# LV.net
KiCad netlist of a schematic drawn in Altium Designer
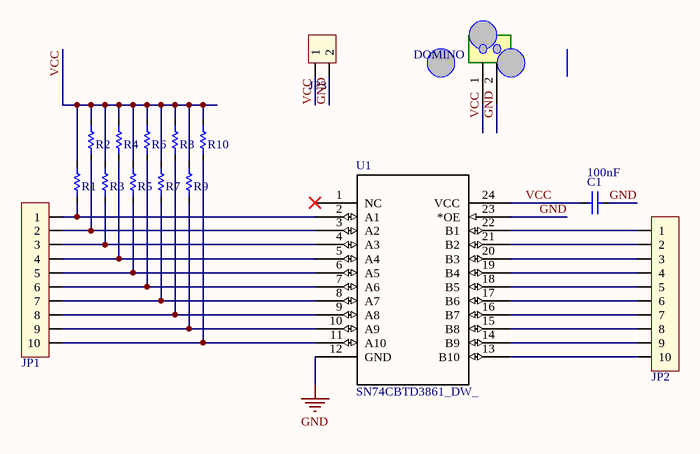
[diagram p0: LV.SchDoc]

(export (version "E")
  (design (tool "Eeschema 10.0.6"))
  (components
    (comp (ref "C1")
      (value "100nF")
      (footprint "0805_C")
      (description "0805 SMD capacitor")
      (libsource (lib "HungIntegrated_Library") (part "C"))
    )
    (comp (ref "D1") (value "DOMINO") (footprint "DOMINO2") (libsource (lib "Thach") (part "Domino 2")))
    (comp (ref "JP1")
      (value "JP10")
      (footprint "HEAD10")
      (description "Connector 10")
      (libsource (lib "") (part "HEAD10_1"))
    )
    (comp (ref "JP2")
      (value "JP10")
      (footprint "HEAD10")
      (description "Connector 10")
      (libsource (lib "Thach") (part "HEAD10"))
    )
    (comp (ref "JP3")
      (value "JP2")
      (footprint "HEAD2")
      (description "Connector 2")
      (libsource (lib "Thach") (part "HEAD2"))
    )
    (comp (ref "R1")
      (value "0805_R")
      (footprint "0805_R")
      (description "0805 SMD resistor")
      (libsource (lib "Thach") (part "0805_R"))
    )
    (comp (ref "R2")
      (value "0805_R")
      (footprint "0805_R")
      (description "0805 SMD resistor")
      (libsource (lib "Thach") (part "0805_R"))
    )
    (comp (ref "R3")
      (value "0805_R")
      (footprint "0805_R")
      (description "0805 SMD resistor")
      (libsource (lib "Thach") (part "0805_R"))
    )
    (comp (ref "R4")
      (value "0805_R")
      (footprint "0805_R")
      (description "0805 SMD resistor")
      (libsource (lib "Thach") (part "0805_R"))
    )
    (comp (ref "R5")
      (value "0805_R")
      (footprint "0805_R")
      (description "0805 SMD resistor")
      (libsource (lib "Thach") (part "0805_R"))
    )
    (comp (ref "R6")
      (value "0805_R")
      (footprint "0805_R")
      (description "0805 SMD resistor")
      (libsource (lib "Thach") (part "0805_R"))
    )
    (comp (ref "R7")
      (value "0805_R")
      (footprint "0805_R")
      (description "0805 SMD resistor")
      (libsource (lib "Thach") (part "0805_R"))
    )
    (comp (ref "R8")
      (value "0805_R")
      (footprint "0805_R")
      (description "0805 SMD resistor")
      (libsource (lib "Thach") (part "0805_R"))
    )
    (comp (ref "R9")
      (value "0805_R")
      (footprint "0805_R")
      (description "0805 SMD resistor")
      (libsource (lib "Thach") (part "0805_R"))
    )
    (comp (ref "R10")
      (value "0805_R")
      (footprint "0805_R")
      (description "0805 SMD resistor")
      (libsource (lib "Thach") (part "0805_R"))
    )
    (comp (ref "U1")
      (value "SN74CBTD3861_DW_")
      (footprint "DW24-M")
      (description "Imported")
      (fields
        (field (name "MANUFACTURER") "Texas Instruments")
        (field (name "GENERIC_PART_NUMBER") "SN74CBTD3861")
      )
      (libsource (lib "Thach") (part "SN74CBTD3861_DW_"))
    )
  )
  (nets
    (net (code "1") (name "/VCC") (class "Default")
      (node (ref "C1") (pin "1") (pinfunction "1_1") (pintype "passive"))
      (node (ref "D1") (pin "1") (pintype "passive"))
      (node (ref "JP3") (pin "1") (pinfunction "1_1") (pintype "passive"))
      (node (ref "R1") (pin "1") (pinfunction "1_1") (pintype "passive"))
      (node (ref "R10") (pin "1") (pinfunction "1_1") (pintype "passive"))
      (node (ref "R2") (pin "1") (pinfunction "1_1") (pintype "passive"))
      (node (ref "R3") (pin "1") (pinfunction "1_1") (pintype "passive"))
      (node (ref "R4") (pin "1") (pinfunction "1_1") (pintype "passive"))
      (node (ref "R5") (pin "1") (pinfunction "1_1") (pintype "passive"))
      (node (ref "R6") (pin "1") (pinfunction "1_1") (pintype "passive"))
      (node (ref "R7") (pin "1") (pinfunction "1_1") (pintype "passive"))
      (node (ref "R8") (pin "1") (pinfunction "1_1") (pintype "passive"))
      (node (ref "R9") (pin "1") (pinfunction "1_1") (pintype "passive"))
      (node (ref "U1") (pin "24") (pinfunction "VCC_24") (pintype "power_in"))
    )
    (net (code "2") (name "GND") (class "Default")
      (node (ref "C1") (pin "2") (pinfunction "2_2") (pintype "passive"))
      (node (ref "D1") (pin "2") (pintype "passive"))
      (node (ref "JP3") (pin "2") (pinfunction "2_2") (pintype "passive"))
      (node (ref "U1") (pin "12") (pinfunction "GND_12") (pintype "power_in"))
      (node (ref "U1") (pin "23") (pinfunction "*OE_23") (pintype "input"))
    )
    (net (code "3") (name "Net-(U1-A1)") (class "Default")
      (node (ref "JP1") (pin "1") (pinfunction "1_1") (pintype "passive"))
      (node (ref "R1") (pin "2") (pinfunction "2_2") (pintype "passive"))
      (node (ref "U1") (pin "2") (pinfunction "A1_2") (pintype "bidirectional"))
    )
    (net (code "4") (name "Net-(U1-A2)") (class "Default")
      (node (ref "JP1") (pin "2") (pinfunction "2_2") (pintype "passive"))
      (node (ref "R2") (pin "2") (pinfunction "2_2") (pintype "passive"))
      (node (ref "U1") (pin "3") (pinfunction "A2_3") (pintype "bidirectional"))
    )
    (net (code "5") (name "Net-(U1-A3)") (class "Default")
      (node (ref "JP1") (pin "3") (pinfunction "3_3") (pintype "passive"))
      (node (ref "R3") (pin "2") (pinfunction "2_2") (pintype "passive"))
      (node (ref "U1") (pin "4") (pinfunction "A3_4") (pintype "bidirectional"))
    )
    (net (code "6") (name "Net-(U1-A4)") (class "Default")
      (node (ref "JP1") (pin "4") (pinfunction "4_4") (pintype "passive"))
      (node (ref "R4") (pin "2") (pinfunction "2_2") (pintype "passive"))
      (node (ref "U1") (pin "5") (pinfunction "A4_5") (pintype "bidirectional"))
    )
    (net (code "7") (name "Net-(U1-A5)") (class "Default")
      (node (ref "JP1") (pin "5") (pinfunction "5_5") (pintype "passive"))
      (node (ref "R5") (pin "2") (pinfunction "2_2") (pintype "passive"))
      (node (ref "U1") (pin "6") (pinfunction "A5_6") (pintype "bidirectional"))
    )
    (net (code "8") (name "Net-(U1-A6)") (class "Default")
      (node (ref "JP1") (pin "6") (pinfunction "6_6") (pintype "passive"))
      (node (ref "R6") (pin "2") (pinfunction "2_2") (pintype "passive"))
      (node (ref "U1") (pin "7") (pinfunction "A6_7") (pintype "bidirectional"))
    )
    (net (code "9") (name "Net-(U1-A7)") (class "Default")
      (node (ref "JP1") (pin "7") (pinfunction "7_7") (pintype "passive"))
      (node (ref "R7") (pin "2") (pinfunction "2_2") (pintype "passive"))
      (node (ref "U1") (pin "8") (pinfunction "A7_8") (pintype "bidirectional"))
    )
    (net (code "10") (name "Net-(U1-A8)") (class "Default")
      (node (ref "JP1") (pin "8") (pinfunction "8_8") (pintype "passive"))
      (node (ref "R8") (pin "2") (pinfunction "2_2") (pintype "passive"))
      (node (ref "U1") (pin "9") (pinfunction "A8_9") (pintype "bidirectional"))
    )
    (net (code "11") (name "Net-(U1-A9)") (class "Default")
      (node (ref "JP1") (pin "9") (pinfunction "9_9") (pintype "passive"))
      (node (ref "R9") (pin "2") (pinfunction "2_2") (pintype "passive"))
      (node (ref "U1") (pin "10") (pinfunction "A9_10") (pintype "bidirectional"))
    )
    (net (code "12") (name "Net-(U1-A10)") (class "Default")
      (node (ref "JP1") (pin "10") (pinfunction "10_10") (pintype "passive"))
      (node (ref "R10") (pin "2") (pinfunction "2_2") (pintype "passive"))
      (node (ref "U1") (pin "11") (pinfunction "A10_11") (pintype "bidirectional"))
    )
    (net (code "13") (name "Net-(U1-B1)") (class "Default")
      (node (ref "JP2") (pin "1") (pinfunction "1_1") (pintype "passive"))
      (node (ref "U1") (pin "22") (pinfunction "B1_22") (pintype "bidirectional"))
    )
    (net (code "14") (name "Net-(U1-B2)") (class "Default")
      (node (ref "JP2") (pin "2") (pinfunction "2_2") (pintype "passive"))
      (node (ref "U1") (pin "21") (pinfunction "B2_21") (pintype "bidirectional"))
    )
    (net (code "15") (name "Net-(U1-B3)") (class "Default")
      (node (ref "JP2") (pin "3") (pinfunction "3_3") (pintype "passive"))
      (node (ref "U1") (pin "20") (pinfunction "B3_20") (pintype "bidirectional"))
    )
    (net (code "16") (name "Net-(U1-B4)") (class "Default")
      (node (ref "JP2") (pin "4") (pinfunction "4_4") (pintype "passive"))
      (node (ref "U1") (pin "19") (pinfunction "B4_19") (pintype "bidirectional"))
    )
    (net (code "17") (name "Net-(U1-B5)") (class "Default")
      (node (ref "JP2") (pin "5") (pinfunction "5_5") (pintype "passive"))
      (node (ref "U1") (pin "18") (pinfunction "B5_18") (pintype "bidirectional"))
    )
    (net (code "18") (name "Net-(U1-B6)") (class "Default")
      (node (ref "JP2") (pin "6") (pinfunction "6_6") (pintype "passive"))
      (node (ref "U1") (pin "17") (pinfunction "B6_17") (pintype "bidirectional"))
    )
    (net (code "19") (name "Net-(U1-B7)") (class "Default")
      (node (ref "JP2") (pin "7") (pinfunction "7_7") (pintype "passive"))
      (node (ref "U1") (pin "16") (pinfunction "B7_16") (pintype "bidirectional"))
    )
    (net (code "20") (name "Net-(U1-B8)") (class "Default")
      (node (ref "JP2") (pin "8") (pinfunction "8_8") (pintype "passive"))
      (node (ref "U1") (pin "15") (pinfunction "B8_15") (pintype "bidirectional"))
    )
    (net (code "21") (name "Net-(U1-B9)") (class "Default")
      (node (ref "JP2") (pin "9") (pinfunction "9_9") (pintype "passive"))
      (node (ref "U1") (pin "14") (pinfunction "B9_14") (pintype "bidirectional"))
    )
    (net (code "22") (name "Net-(U1-B10)") (class "Default")
      (node (ref "JP2") (pin "10") (pinfunction "10_10") (pintype "passive"))
      (node (ref "U1") (pin "13") (pinfunction "B10_13") (pintype "bidirectional"))
    )
    (net (code "23") (name "unconnected-(U1-NC-Pad1)") (class "Default")
      (node (ref "U1") (pin "1") (pinfunction "NC_1") (pintype "passive+no_connect"))
    )
  )
)
